# OpenAir.net
KiCad netlist of a schematic drawn in EAGLE
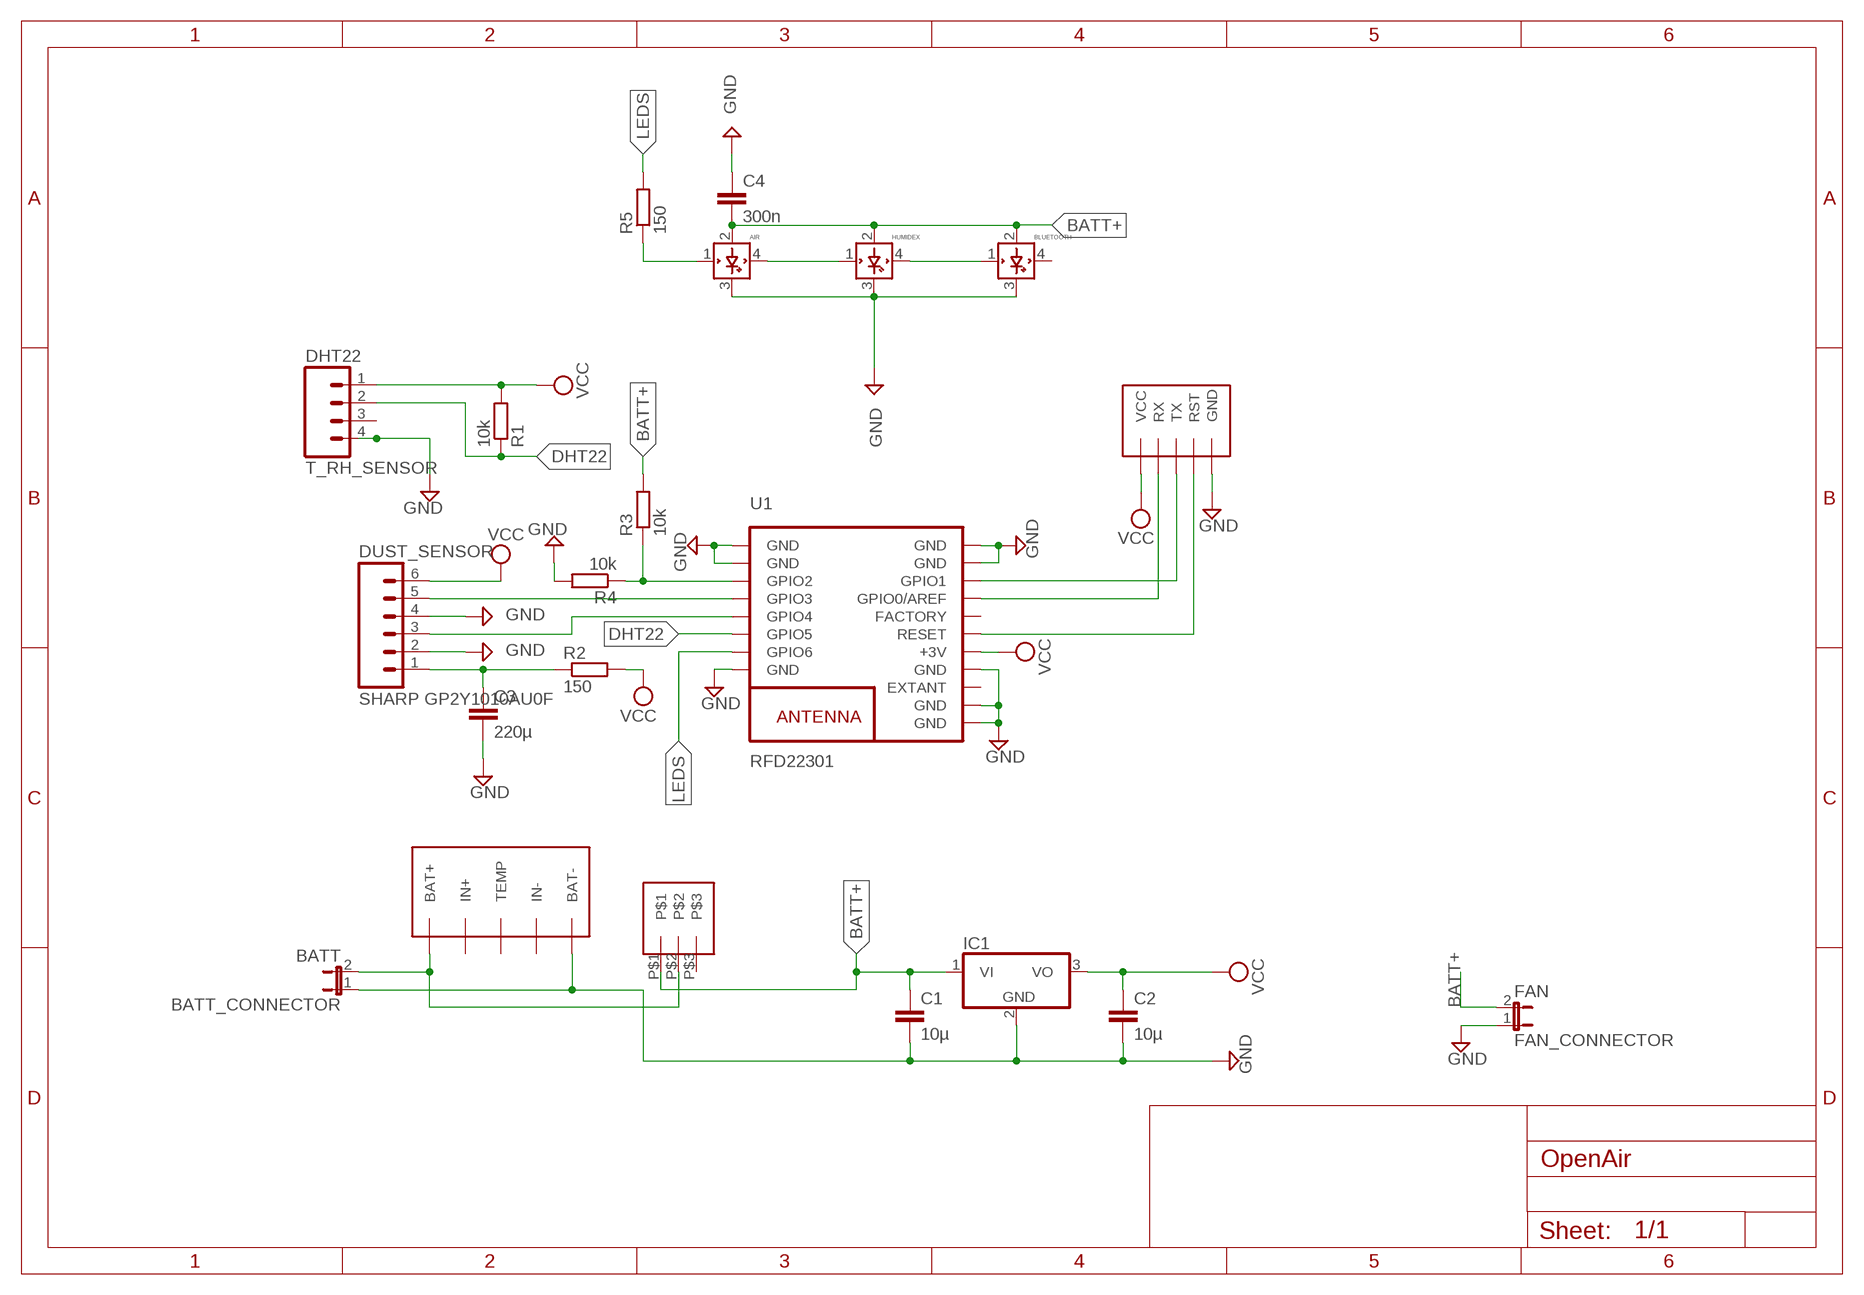
[diagram p0: schematic, sheet 1]

(export (version "E")
  (design (tool "Eeschema 10.0.6"))
  (components
    (comp (ref "AIR")
      (value "WS2812BRGB")
      (footprint "eagle-import:LED5MMRGB")
      (libsource (lib "eagle-import") (part "WS2812BRGB"))
    )
    (comp (ref "BATT_CONNECTOR")
      (value "BATT")
      (footprint "eagle-import:JP1")
      (libsource (lib "eagle-import") (part "JP1E"))
    )
    (comp (ref "BLUETOOTH")
      (value "WS2812BRGB")
      (footprint "eagle-import:LED5MMRGB")
      (libsource (lib "eagle-import") (part "WS2812BRGB"))
    )
    (comp (ref "C1")
      (value "10µ")
      (footprint "eagle-import:C025-030X050")
      (libsource (lib "eagle-import") (part "C-EU025-030X050"))
    )
    (comp (ref "C2")
      (value "10µ")
      (footprint "eagle-import:C025-030X050")
      (libsource (lib "eagle-import") (part "C-EU025-030X050"))
    )
    (comp (ref "C3")
      (value "220µ")
      (footprint "eagle-import:C025-030X050")
      (libsource (lib "eagle-import") (part "C-EU025-030X050"))
    )
    (comp (ref "C4")
      (value "300n")
      (footprint "eagle-import:C025-030X050")
      (libsource (lib "eagle-import") (part "C-EU025-030X050"))
    )
    (comp (ref "DUST_SENSOR")
      (value "SHARP GP2Y1010AU0F")
      (footprint "eagle-import:1X06_LONGPADS")
      (libsource (lib "eagle-import") (part "M06LONGPADS"))
    )
    (comp (ref "FAN_CONNECTOR")
      (value "FAN")
      (footprint "eagle-import:JP1")
      (libsource (lib "eagle-import") (part "JP1E"))
    )
    (comp (ref "HUMIDEX")
      (value "WS2812BRGB")
      (footprint "eagle-import:LED5MMRGB")
      (libsource (lib "eagle-import") (part "WS2812BRGB"))
    )
    (comp (ref "IC1")
      (value "78T")
      (footprint "eagle-import:TO220H")
      (libsource (lib "eagle-import") (part "78T05"))
    )
    (comp (ref "R1")
      (value "10k")
      (footprint "eagle-import:0207_10")
      (libsource (lib "eagle-import") (part "R-EU_0207/10"))
    )
    (comp (ref "R2")
      (value "150")
      (footprint "eagle-import:0207_10")
      (libsource (lib "eagle-import") (part "R-EU_0207/10"))
    )
    (comp (ref "R3")
      (value "10k")
      (footprint "eagle-import:0207_10")
      (libsource (lib "eagle-import") (part "R-EU_0207/10"))
    )
    (comp (ref "R4")
      (value "10k")
      (footprint "eagle-import:0207_10")
      (libsource (lib "eagle-import") (part "R-EU_0207/10"))
    )
    (comp (ref "R5")
      (value "150")
      (footprint "eagle-import:0207_10")
      (libsource (lib "eagle-import") (part "R-EU_0207/10"))
    )
    (comp (ref "T_RH_SENSOR")
      (value "DHT22")
      (footprint "eagle-import:JST-4-PTH-VERT")
      (libsource (lib "eagle-import") (part "M04JST-PTH-VERT"))
    )
    (comp (ref "U$1")
      (value "IC_PROG")
      (footprint "eagle-import:IC_PROG")
      (libsource (lib "eagle-import") (part "IC_PROG"))
    )
    (comp (ref "U$4")
      (value "BATT_CHARG")
      (footprint "eagle-import:BATT_CHARG")
      (libsource (lib "eagle-import") (part "BATT_CHARG"))
    )
    (comp (ref "U$5")
      (value "SPSTCUSTOM")
      (footprint "eagle-import:SPSTCUSTOM")
      (libsource (lib "eagle-import") (part "SPSTCUSTOM"))
    )
    (comp (ref "U1")
      (value "RFD22301")
      (footprint "eagle-import:RFD22301")
      (libsource (lib "eagle-import") (part "RFD22301"))
    )
  )
  (nets
    (net (code "1") (name "BATT+") (class "Default")
      (node (ref "AIR") (pin "2") (pinfunction "VDD_2") (pintype "bidirectional"))
      (node (ref "BLUETOOTH") (pin "2") (pinfunction "VDD_2") (pintype "bidirectional"))
      (node (ref "C1") (pin "1") (pinfunction "1_1") (pintype "passive"))
      (node (ref "C4") (pin "2") (pinfunction "2_2") (pintype "passive"))
      (node (ref "FAN_CONNECTOR") (pin "2") (pinfunction "2_2") (pintype "passive"))
      (node (ref "HUMIDEX") (pin "2") (pinfunction "VDD_2") (pintype "bidirectional"))
      (node (ref "IC1") (pin "1") (pinfunction "VI_1") (pintype "input"))
      (node (ref "R3") (pin "2") (pinfunction "2_2") (pintype "passive"))
      (node (ref "U$5") (pin "P$1") (pinfunction "P$1_P$1") (pintype "bidirectional"))
    )
    (net (code "2") (name "DHT22") (class "Default")
      (node (ref "R1") (pin "1") (pinfunction "1_1") (pintype "passive"))
      (node (ref "T_RH_SENSOR") (pin "2") (pinfunction "2_2") (pintype "passive"))
      (node (ref "U1") (pin "6") (pinfunction "GPIO5_6") (pintype "bidirectional"))
    )
    (net (code "3") (name "GND") (class "Default")
      (node (ref "AIR") (pin "3") (pinfunction "GND_3") (pintype "bidirectional"))
      (node (ref "BATT_CONNECTOR") (pin "1") (pinfunction "1_1") (pintype "passive"))
      (node (ref "BLUETOOTH") (pin "3") (pinfunction "GND_3") (pintype "bidirectional"))
      (node (ref "C1") (pin "2") (pinfunction "2_2") (pintype "passive"))
      (node (ref "C2") (pin "2") (pinfunction "2_2") (pintype "passive"))
      (node (ref "C3") (pin "2") (pinfunction "2_2") (pintype "passive"))
      (node (ref "C4") (pin "1") (pinfunction "1_1") (pintype "passive"))
      (node (ref "DUST_SENSOR") (pin "2") (pinfunction "2_2") (pintype "passive"))
      (node (ref "DUST_SENSOR") (pin "4") (pinfunction "4_4") (pintype "passive"))
      (node (ref "FAN_CONNECTOR") (pin "1") (pinfunction "1_1") (pintype "passive"))
      (node (ref "HUMIDEX") (pin "3") (pinfunction "GND_3") (pintype "bidirectional"))
      (node (ref "IC1") (pin "2") (pinfunction "GND_2") (pintype "passive"))
      (node (ref "R4") (pin "2") (pinfunction "2_2") (pintype "passive"))
      (node (ref "T_RH_SENSOR") (pin "4") (pinfunction "4_4") (pintype "passive"))
      (node (ref "U$1") (pin "GND") (pinfunction "GND_GND") (pintype "bidirectional"))
      (node (ref "U$4") (pin "BAT-") (pinfunction "BAT-_BAT-") (pintype "bidirectional"))
      (node (ref "U1") (pin "1") (pinfunction "GND_1") (pintype "power_in"))
      (node (ref "U1") (pin "10") (pinfunction "GND_10") (pintype "power_in"))
      (node (ref "U1") (pin "12") (pinfunction "GND_12") (pintype "power_in"))
      (node (ref "U1") (pin "18") (pinfunction "GND_18") (pintype "power_in"))
      (node (ref "U1") (pin "19") (pinfunction "GND_19") (pintype "power_in"))
      (node (ref "U1") (pin "2") (pinfunction "GND_2") (pintype "power_in"))
      (node (ref "U1") (pin "8") (pinfunction "GND_8") (pintype "power_in"))
      (node (ref "U1") (pin "9") (pinfunction "GND_9") (pintype "power_in"))
    )
    (net (code "4") (name "LEDS") (class "Default")
      (node (ref "R5") (pin "2") (pinfunction "2_2") (pintype "passive"))
      (node (ref "U1") (pin "7") (pinfunction "GPIO6_7") (pintype "bidirectional"))
    )
    (net (code "5") (name "Net-(AIR-DIN)") (class "Default")
      (node (ref "AIR") (pin "1") (pinfunction "DIN_1") (pintype "input"))
      (node (ref "R5") (pin "1") (pinfunction "1_1") (pintype "passive"))
    )
    (net (code "6") (name "Net-(AIR-DOUT)") (class "Default")
      (node (ref "AIR") (pin "4") (pinfunction "DOUT_4") (pintype "output"))
      (node (ref "HUMIDEX") (pin "1") (pinfunction "DIN_1") (pintype "input"))
    )
    (net (code "7") (name "Net-(BATT_CONNECTOR-Pad2)") (class "Default")
      (node (ref "BATT_CONNECTOR") (pin "2") (pinfunction "2_2") (pintype "passive"))
      (node (ref "U$4") (pin "BAT+") (pinfunction "BAT+_BAT+") (pintype "bidirectional"))
      (node (ref "U$5") (pin "P$2") (pinfunction "P$2_P$2") (pintype "bidirectional"))
    )
    (net (code "8") (name "Net-(BLUETOOTH-DIN)") (class "Default")
      (node (ref "BLUETOOTH") (pin "1") (pinfunction "DIN_1") (pintype "input"))
      (node (ref "HUMIDEX") (pin "4") (pinfunction "DOUT_4") (pintype "output"))
    )
    (net (code "9") (name "Net-(C3-Pad1)") (class "Default")
      (node (ref "C3") (pin "1") (pinfunction "1_1") (pintype "passive"))
      (node (ref "DUST_SENSOR") (pin "1") (pinfunction "1_1") (pintype "passive"))
      (node (ref "R2") (pin "1") (pinfunction "1_1") (pintype "passive"))
    )
    (net (code "10") (name "Net-(U1-GPIO0{slash}AREF)") (class "Default")
      (node (ref "U$1") (pin "RX") (pinfunction "RX_RX") (pintype "bidirectional"))
      (node (ref "U1") (pin "16") (pinfunction "GPIO0/AREF_16") (pintype "bidirectional"))
    )
    (net (code "11") (name "Net-(U1-GPIO1)") (class "Default")
      (node (ref "U$1") (pin "TX") (pinfunction "TX_TX") (pintype "bidirectional"))
      (node (ref "U1") (pin "17") (pinfunction "GPIO1_17") (pintype "bidirectional"))
    )
    (net (code "12") (name "Net-(U1-GPIO2)") (class "Default")
      (node (ref "R3") (pin "1") (pinfunction "1_1") (pintype "passive"))
      (node (ref "R4") (pin "1") (pinfunction "1_1") (pintype "passive"))
      (node (ref "U1") (pin "3") (pinfunction "GPIO2_3") (pintype "bidirectional"))
    )
    (net (code "13") (name "Net-(U1-GPIO3)") (class "Default")
      (node (ref "DUST_SENSOR") (pin "5") (pinfunction "5_5") (pintype "passive"))
      (node (ref "U1") (pin "4") (pinfunction "GPIO3_4") (pintype "bidirectional"))
    )
    (net (code "14") (name "Net-(U1-GPIO4)") (class "Default")
      (node (ref "DUST_SENSOR") (pin "3") (pinfunction "3_3") (pintype "passive"))
      (node (ref "U1") (pin "5") (pinfunction "GPIO4_5") (pintype "bidirectional"))
    )
    (net (code "15") (name "Net-(U1-RESET)") (class "Default")
      (node (ref "U$1") (pin "RST") (pinfunction "RST_RST") (pintype "bidirectional"))
      (node (ref "U1") (pin "14") (pinfunction "RESET_14") (pintype "bidirectional"))
    )
    (net (code "16") (name "VCC") (class "Default")
      (node (ref "C2") (pin "1") (pinfunction "1_1") (pintype "passive"))
      (node (ref "DUST_SENSOR") (pin "6") (pinfunction "6_6") (pintype "passive"))
      (node (ref "IC1") (pin "3") (pinfunction "VO_3") (pintype "passive"))
      (node (ref "R1") (pin "2") (pinfunction "2_2") (pintype "passive"))
      (node (ref "R2") (pin "2") (pinfunction "2_2") (pintype "passive"))
      (node (ref "T_RH_SENSOR") (pin "1") (pinfunction "1_1") (pintype "passive"))
      (node (ref "U$1") (pin "VCC") (pinfunction "VCC_VCC") (pintype "bidirectional"))
      (node (ref "U1") (pin "13") (pinfunction "+3V_13") (pintype "power_in"))
    )
    (net (code "17") (name "unconnected-(BLUETOOTH-DOUT-Pad4)") (class "Default")
      (node (ref "BLUETOOTH") (pin "4") (pinfunction "DOUT_4") (pintype "output"))
    )
    (net (code "18") (name "unconnected-(T_RH_SENSOR-Pad3)") (class "Default")
      (node (ref "T_RH_SENSOR") (pin "3") (pinfunction "3_3") (pintype "passive"))
    )
    (net (code "19") (name "unconnected-(U$4-PadIN+)") (class "Default")
      (node (ref "U$4") (pin "IN+") (pinfunction "IN+_IN+") (pintype "bidirectional"))
    )
    (net (code "20") (name "unconnected-(U$4-PadIN-)") (class "Default")
      (node (ref "U$4") (pin "IN-") (pinfunction "IN-_IN-") (pintype "bidirectional"))
    )
    (net (code "21") (name "unconnected-(U$4-PadTEMP)") (class "Default")
      (node (ref "U$4") (pin "TEMP") (pinfunction "TEMP_TEMP") (pintype "bidirectional"))
    )
    (net (code "22") (name "unconnected-(U$5-PadP$3)") (class "Default")
      (node (ref "U$5") (pin "P$3") (pinfunction "P$3_P$3") (pintype "bidirectional"))
    )
    (net (code "23") (name "unconnected-(U1-EXTANT-Pad11)") (class "Default")
      (node (ref "U1") (pin "11") (pinfunction "EXTANT_11") (pintype "no_connect"))
    )
    (net (code "24") (name "unconnected-(U1-FACTORY-Pad15)") (class "Default")
      (node (ref "U1") (pin "15") (pinfunction "FACTORY_15") (pintype "bidirectional"))
    )
  )
)
